# Pure_Digit.net
KiCad netlist of a schematic drawn in EAGLE
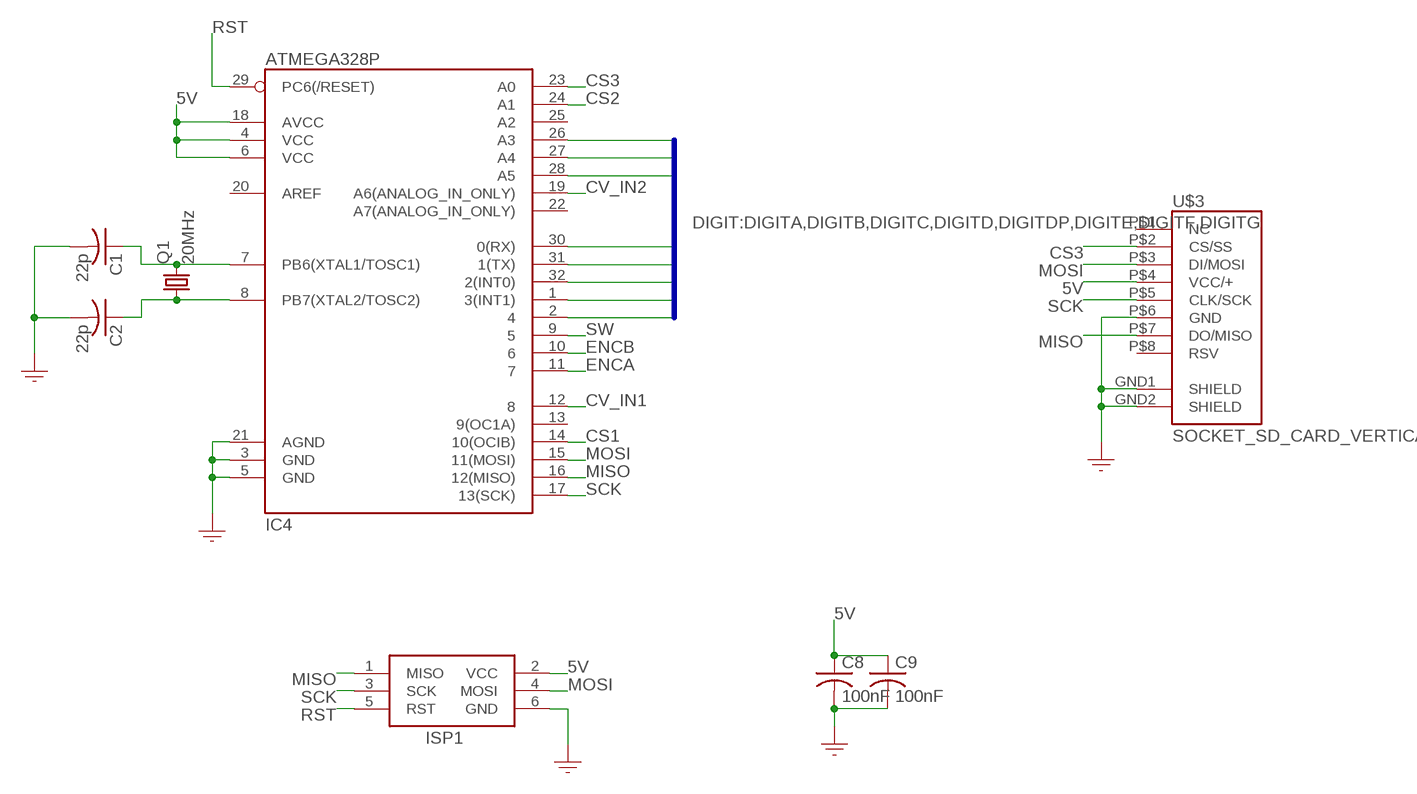
[diagram p0: schematic, sheet 1]
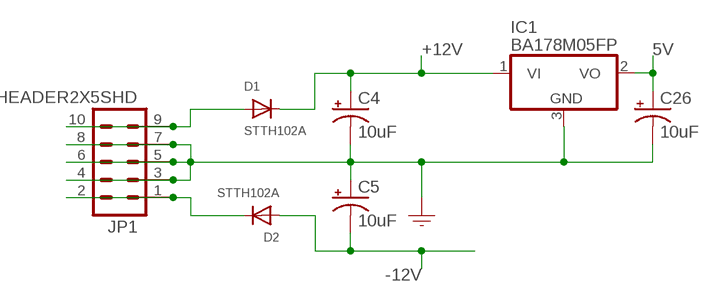
[diagram p1: schematic, sheet 2]
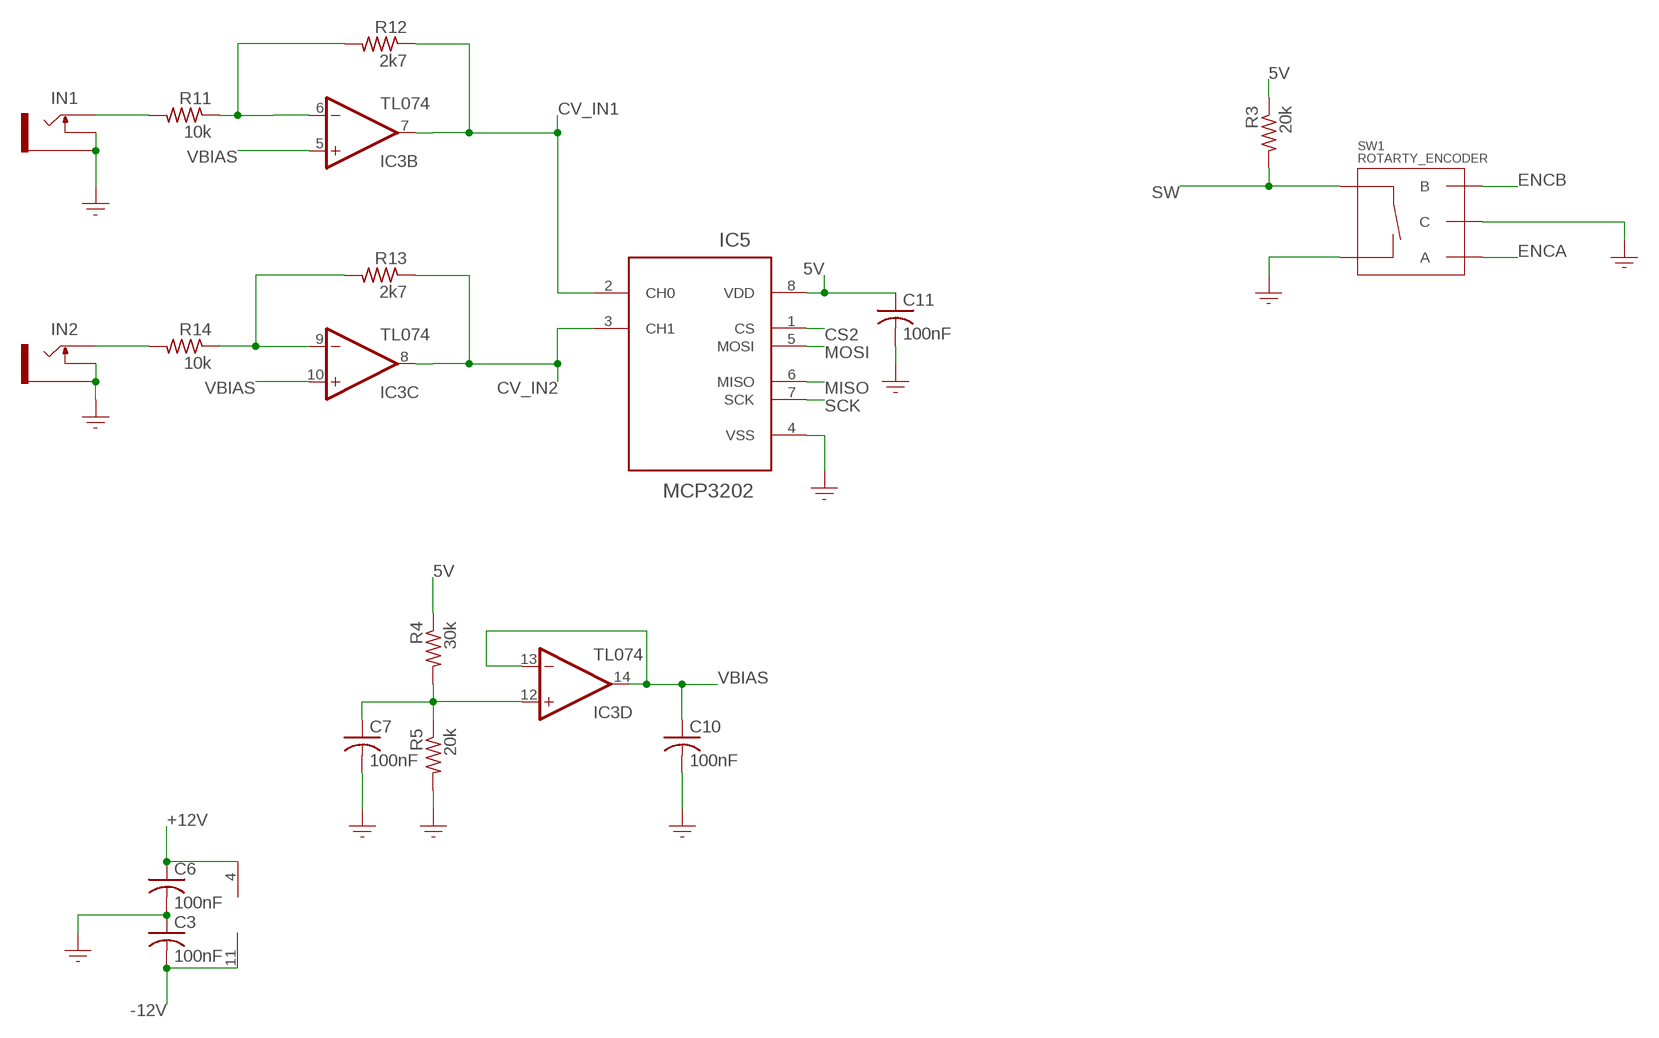
[diagram p2: schematic, sheet 3]
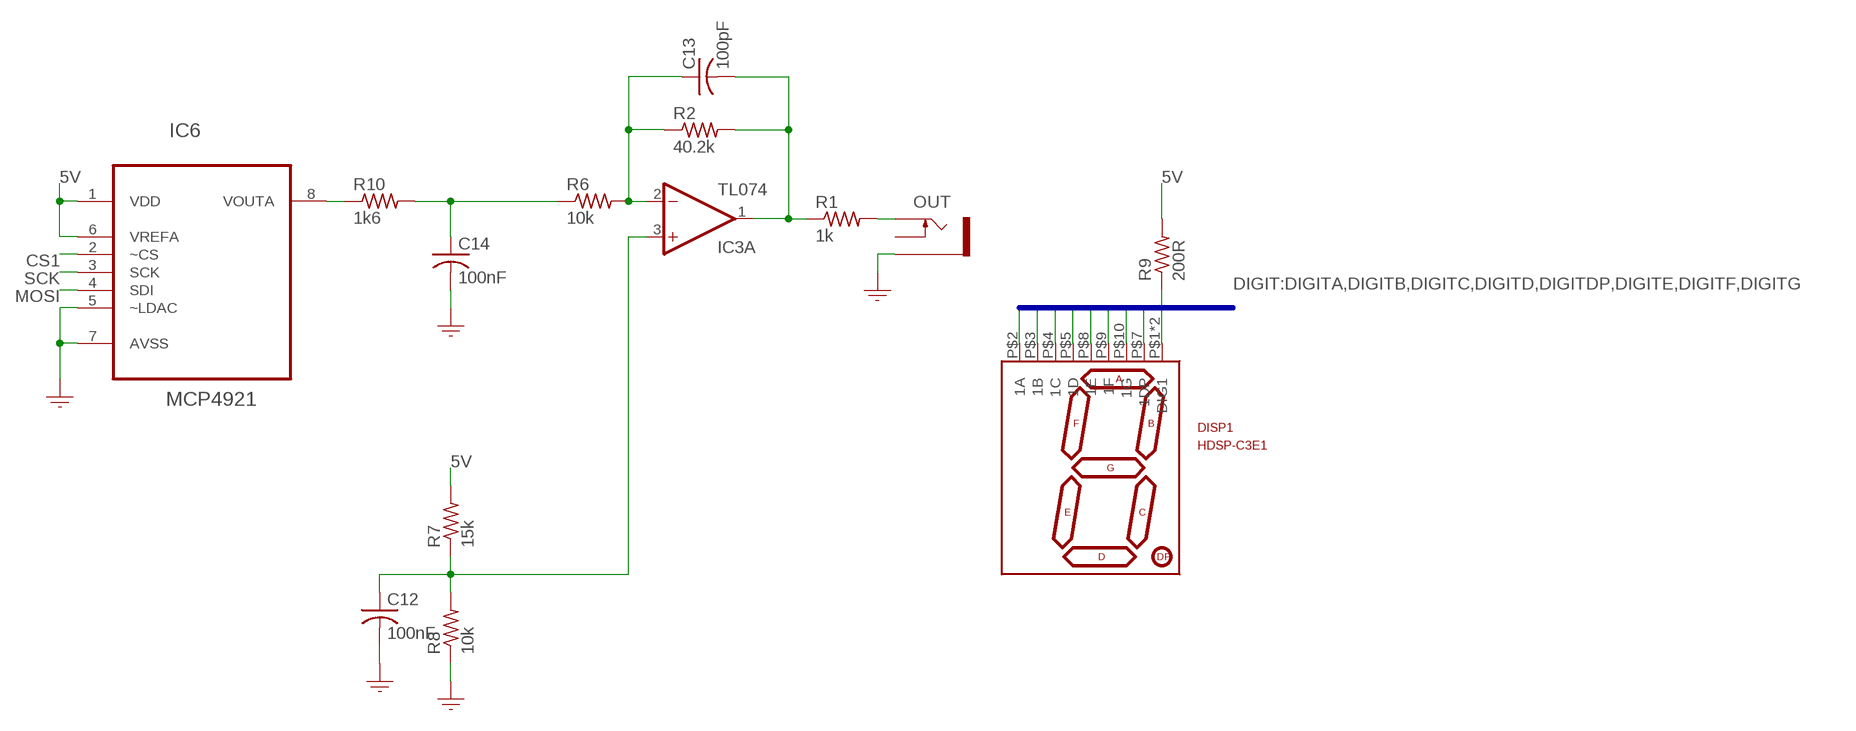
[diagram p3: schematic, sheet 4]

(export (version "E")
  (design (tool "Eeschema 10.0.6"))
  (components
    (comp (ref "C12")
      (value "100nF")
      (footprint "eagle-import:C0805")
      (libsource (lib "eagle-import") (part "CAPACITOR-USC0805"))
    )
    (comp (ref "C13")
      (value "100pF")
      (footprint "eagle-import:C0805")
      (libsource (lib "eagle-import") (part "CAPACITOR-USC0805"))
    )
    (comp (ref "C14")
      (value "100nF")
      (footprint "eagle-import:C0805")
      (libsource (lib "eagle-import") (part "CAPACITOR-USC0805"))
    )
    (comp (ref "DISP1")
      (value "HDSP-C3E1")
      (footprint "eagle-import:7-SEGMENT-1DIGIT")
      (libsource (lib "eagle-import") (part "DISPLAY_7-SEGMENT-1DIGIT"))
    )
    (comp (ref "IC3")
      (value "TL074")
      (footprint "eagle-import:SO14")
      (libsource (lib "eagle-import") (part "OPAMP_QUADD"))
    )
    (comp (ref "IC6")
      (value "MCP4921")
      (footprint "eagle-import:SOIC8")
      (libsource (lib "eagle-import") (part "DAC_SINGLE_12B_MCP4921"))
    )
    (comp (ref "OUT")
      (value "PJ301M-12")
      (footprint "eagle-import:PJ301M-12")
      (libsource (lib "eagle-import") (part "SOCKET_MONO_3.5MMPJ301M-12"))
    )
    (comp (ref "R1")
      (value "1k")
      (footprint "eagle-import:R0805")
      (libsource (lib "eagle-import") (part "RESISTOR_USR0805"))
    )
    (comp (ref "R2")
      (value "40.2k")
      (footprint "eagle-import:R0805")
      (libsource (lib "eagle-import") (part "RESISTOR_USR0805"))
    )
    (comp (ref "R6")
      (value "10k")
      (footprint "eagle-import:R0805")
      (libsource (lib "eagle-import") (part "RESISTOR_USR0805"))
    )
    (comp (ref "R7")
      (value "15k")
      (footprint "eagle-import:R0805")
      (libsource (lib "eagle-import") (part "RESISTOR_USR0805"))
    )
    (comp (ref "R8")
      (value "10k")
      (footprint "eagle-import:R0805")
      (libsource (lib "eagle-import") (part "RESISTOR_USR0805"))
    )
    (comp (ref "R9")
      (value "200R")
      (footprint "eagle-import:R0805")
      (libsource (lib "eagle-import") (part "RESISTOR_USR0805"))
    )
    (comp (ref "R10")
      (value "1k6")
      (footprint "eagle-import:R0805")
      (libsource (lib "eagle-import") (part "RESISTOR_USR0805"))
    )
    (comp (ref "C3")
      (value "100nF")
      (footprint "eagle-import:C0805")
      (libsource (lib "eagle-import") (part "CAPACITOR-USC0805"))
    )
    (comp (ref "C6")
      (value "100nF")
      (footprint "eagle-import:C0805")
      (libsource (lib "eagle-import") (part "CAPACITOR-USC0805"))
    )
    (comp (ref "C7")
      (value "100nF")
      (footprint "eagle-import:C0805")
      (libsource (lib "eagle-import") (part "CAPACITOR-USC0805"))
    )
    (comp (ref "C10")
      (value "100nF")
      (footprint "eagle-import:C0805")
      (libsource (lib "eagle-import") (part "CAPACITOR-USC0805"))
    )
    (comp (ref "C11")
      (value "100nF")
      (footprint "eagle-import:C0805")
      (libsource (lib "eagle-import") (part "CAPACITOR-USC0805"))
    )
    (comp (ref "IC5")
      (value "MCP3202")
      (footprint "eagle-import:SOIC--8")
      (libsource (lib "eagle-import") (part "ADC_DUAL_12B_MCP3202"))
    )
    (comp (ref "IN1")
      (value "PJ301M-12")
      (footprint "eagle-import:PJ301M-12")
      (libsource (lib "eagle-import") (part "SOCKET_MONO_3.5MMPJ301M-12"))
    )
    (comp (ref "IN2")
      (value "PJ301M-12")
      (footprint "eagle-import:PJ301M-12")
      (libsource (lib "eagle-import") (part "SOCKET_MONO_3.5MMPJ301M-12"))
    )
    (comp (ref "R3")
      (value "20k")
      (footprint "eagle-import:R0805")
      (libsource (lib "eagle-import") (part "RESISTOR_USR0805"))
    )
    (comp (ref "R4")
      (value "30k")
      (footprint "eagle-import:R0805")
      (libsource (lib "eagle-import") (part "RESISTOR_USR0805"))
    )
    (comp (ref "R5")
      (value "20k")
      (footprint "eagle-import:R0805")
      (libsource (lib "eagle-import") (part "RESISTOR_USR0805"))
    )
    (comp (ref "R11")
      (value "10k")
      (footprint "eagle-import:R0805")
      (libsource (lib "eagle-import") (part "RESISTOR_USR0805"))
    )
    (comp (ref "R12")
      (value "2k7")
      (footprint "eagle-import:R0805")
      (libsource (lib "eagle-import") (part "RESISTOR_USR0805"))
    )
    (comp (ref "R13")
      (value "2k7")
      (footprint "eagle-import:R0805")
      (libsource (lib "eagle-import") (part "RESISTOR_USR0805"))
    )
    (comp (ref "R14")
      (value "10k")
      (footprint "eagle-import:R0805")
      (libsource (lib "eagle-import") (part "RESISTOR_USR0805"))
    )
    (comp (ref "SW1")
      (value "ROTARTY_ENCODER")
      (footprint "eagle-import:ROTARY_ENC_PLAIN")
      (libsource (lib "eagle-import") (part "ROTARTY_ENCODER"))
    )
    (comp (ref "C4")
      (value "10uF")
      (footprint "eagle-import:153CLV-0505")
      (libsource (lib "eagle-import") (part "CAPACITOR_POL-US153CLV-0505"))
    )
    (comp (ref "C5")
      (value "10uF")
      (footprint "eagle-import:153CLV-0505")
      (libsource (lib "eagle-import") (part "CAPACITOR_POL-US153CLV-0505"))
    )
    (comp (ref "C26")
      (value "10uF")
      (footprint "eagle-import:153CLV-0505")
      (libsource (lib "eagle-import") (part "CAPACITOR_POL-US153CLV-0505"))
    )
    (comp (ref "D1")
      (value "STTH102A")
      (footprint "eagle-import:SMADIODE")
      (libsource (lib "eagle-import") (part "DIODESMA"))
    )
    (comp (ref "D2")
      (value "STTH102A")
      (footprint "eagle-import:SMADIODE")
      (libsource (lib "eagle-import") (part "DIODESMA"))
    )
    (comp (ref "IC1")
      (value "BA178M05FP")
      (footprint "eagle-import:TO252")
      (libsource (lib "eagle-import") (part "VOLTAGE_REG_POSDT05"))
    )
    (comp (ref "JP1")
      (value "HEADER2X5SHD")
      (footprint "eagle-import:2X5-SHROUDED")
      (libsource (lib "eagle-import") (part "HEADER2X5SHD"))
    )
    (comp (ref "C1")
      (value "22p")
      (footprint "eagle-import:C0805")
      (libsource (lib "eagle-import") (part "CAPACITOR-USC0805"))
    )
    (comp (ref "C2")
      (value "22p")
      (footprint "eagle-import:C0805")
      (libsource (lib "eagle-import") (part "CAPACITOR-USC0805"))
    )
    (comp (ref "C8")
      (value "100nF")
      (footprint "eagle-import:C0805")
      (libsource (lib "eagle-import") (part "CAPACITOR-USC0805"))
    )
    (comp (ref "C9")
      (value "100nF")
      (footprint "eagle-import:C0805")
      (libsource (lib "eagle-import") (part "CAPACITOR-USC0805"))
    )
    (comp (ref "IC4")
      (value "ATMEGA328P")
      (footprint "eagle-import:TQFP32-08")
      (libsource (lib "eagle-import") (part "MICROPROCESSOR_ATMEGA328_SMT"))
    )
    (comp (ref "ISP1")
      (value "HEADER2X3-6")
      (footprint "eagle-import:AVRISP")
      (libsource (lib "eagle-import") (part "HEADER2X3-6"))
    )
    (comp (ref "Q1")
      (value "20MHz")
      (footprint "eagle-import:SM49")
      (libsource (lib "eagle-import") (part "CRYSTALSM49"))
    )
    (comp (ref "U$3")
      (value "SOCKET_SD_CARD_VERTICAL")
      (footprint "eagle-import:PJS008U-3000")
      (libsource (lib "eagle-import") (part "SOCKET_SD_CARD_VERTICAL"))
    )
  )
  (nets
    (net (code "3") (name "+12V") (class "Default")
      (node (ref "C4") (pin "+") (pinfunction "+_+") (pintype "passive"))
      (node (ref "C6") (pin "1") (pinfunction "1_1") (pintype "passive"))
      (node (ref "D1") (pin "C") (pinfunction "C_C") (pintype "passive"))
      (node (ref "IC1") (pin "1") (pinfunction "VI_1") (pintype "input"))
      (node (ref "IC3") (pin "4") (pinfunction "V+_4") (pintype "power_in"))
    )
    (net (code "4") (name "-12V") (class "Default")
      (node (ref "C3") (pin "2") (pinfunction "2_2") (pintype "passive"))
      (node (ref "C5") (pin "-") (pinfunction "-_-") (pintype "passive"))
      (node (ref "D2") (pin "A") (pinfunction "A_A") (pintype "passive"))
      (node (ref "IC3") (pin "11") (pinfunction "V-_11") (pintype "power_in"))
    )
    (net (code "7") (name "5V") (class "Default")
      (node (ref "C11") (pin "1") (pinfunction "1_1") (pintype "passive"))
      (node (ref "C26") (pin "+") (pinfunction "+_+") (pintype "passive"))
      (node (ref "C8") (pin "1") (pinfunction "1_1") (pintype "passive"))
      (node (ref "C9") (pin "1") (pinfunction "1_1") (pintype "passive"))
      (node (ref "IC1") (pin "2") (pinfunction "VO_2") (pintype "passive"))
      (node (ref "IC4") (pin "18") (pinfunction "AVCC_18") (pintype "bidirectional"))
      (node (ref "IC4") (pin "4") (pinfunction "VCC_4") (pintype "bidirectional"))
      (node (ref "IC4") (pin "6") (pinfunction "VCC_6") (pintype "bidirectional"))
      (node (ref "IC5") (pin "8") (pinfunction "VDD_8") (pintype "bidirectional"))
      (node (ref "IC6") (pin "1") (pinfunction "VDD_1") (pintype "power_in"))
      (node (ref "IC6") (pin "6") (pinfunction "VREFA_6") (pintype "input"))
      (node (ref "ISP1") (pin "2") (pinfunction "VCC_2") (pintype "power_in"))
      (node (ref "R3") (pin "1") (pinfunction "1_1") (pintype "passive"))
      (node (ref "R4") (pin "1") (pinfunction "1_1") (pintype "passive"))
      (node (ref "R7") (pin "2") (pinfunction "2_2") (pintype "passive"))
      (node (ref "R9") (pin "2") (pinfunction "2_2") (pintype "passive"))
      (node (ref "U$3") (pin "P$4") (pinfunction "VCC/+_P$4") (pintype "bidirectional"))
    )
    (net (code "8") (name "CS1") (class "Default")
      (node (ref "IC4") (pin "14") (pinfunction "10(OCIB)_14") (pintype "bidirectional"))
      (node (ref "IC6") (pin "2") (pinfunction "~{CS}_2") (pintype "input"))
    )
    (net (code "9") (name "CS2") (class "Default")
      (node (ref "IC4") (pin "24") (pinfunction "A1_24") (pintype "bidirectional"))
      (node (ref "IC5") (pin "1") (pinfunction "CS_1") (pintype "bidirectional"))
    )
    (net (code "10") (name "CS3") (class "Default")
      (node (ref "IC4") (pin "23") (pinfunction "A0_23") (pintype "bidirectional"))
      (node (ref "U$3") (pin "P$2") (pinfunction "CS/SS_P$2") (pintype "bidirectional"))
    )
    (net (code "11") (name "CV_IN1") (class "Default")
      (node (ref "IC3") (pin "7") (pinfunction "OUT_7") (pintype "output"))
      (node (ref "IC4") (pin "12") (pinfunction "8_12") (pintype "bidirectional"))
      (node (ref "IC5") (pin "2") (pinfunction "CH0_2") (pintype "bidirectional"))
      (node (ref "R12") (pin "1") (pinfunction "1_1") (pintype "passive"))
    )
    (net (code "12") (name "CV_IN2") (class "Default")
      (node (ref "IC3") (pin "8") (pinfunction "OUT_8") (pintype "output"))
      (node (ref "IC4") (pin "19") (pinfunction "A6(ANALOG_IN_ONLY)_19") (pintype "bidirectional"))
      (node (ref "IC5") (pin "3") (pinfunction "CH1_3") (pintype "bidirectional"))
      (node (ref "R13") (pin "1") (pinfunction "1_1") (pintype "passive"))
    )
    (net (code "13") (name "DIGITA") (class "Default")
      (node (ref "DISP1") (pin "P$2") (pinfunction "1A_P$2") (pintype "bidirectional"))
      (node (ref "IC4") (pin "30") (pinfunction "0(RX)_30") (pintype "bidirectional"))
    )
    (net (code "14") (name "DIGITB") (class "Default")
      (node (ref "DISP1") (pin "P$3") (pinfunction "1B_P$3") (pintype "bidirectional"))
      (node (ref "IC4") (pin "28") (pinfunction "A5_28") (pintype "bidirectional"))
    )
    (net (code "15") (name "DIGITC") (class "Default")
      (node (ref "DISP1") (pin "P$4") (pinfunction "1C_P$4") (pintype "bidirectional"))
      (node (ref "IC4") (pin "27") (pinfunction "A4_27") (pintype "bidirectional"))
    )
    (net (code "16") (name "DIGITD") (class "Default")
      (node (ref "DISP1") (pin "P$5") (pinfunction "1D_P$5") (pintype "bidirectional"))
      (node (ref "IC4") (pin "26") (pinfunction "A3_26") (pintype "bidirectional"))
    )
    (net (code "17") (name "DIGITDP") (class "Default")
      (node (ref "DISP1") (pin "P$7") (pinfunction "1DP_P$7") (pintype "bidirectional"))
      (node (ref "IC4") (pin "1") (pinfunction "3(INT1)_1") (pintype "bidirectional"))
    )
    (net (code "18") (name "DIGITE") (class "Default")
      (node (ref "DISP1") (pin "P$8") (pinfunction "1E_P$8") (pintype "bidirectional"))
      (node (ref "IC4") (pin "2") (pinfunction "4_2") (pintype "bidirectional"))
    )
    (net (code "19") (name "DIGITF") (class "Default")
      (node (ref "DISP1") (pin "P$9") (pinfunction "1F_P$9") (pintype "bidirectional"))
      (node (ref "IC4") (pin "32") (pinfunction "2(INT0)_32") (pintype "bidirectional"))
    )
    (net (code "20") (name "DIGITG") (class "Default")
      (node (ref "DISP1") (pin "P$10") (pinfunction "1G_P$10") (pintype "bidirectional"))
      (node (ref "IC4") (pin "31") (pinfunction "1(TX)_31") (pintype "bidirectional"))
    )
    (net (code "21") (name "ENCA") (class "Default")
      (node (ref "IC4") (pin "11") (pinfunction "7_11") (pintype "bidirectional"))
      (node (ref "SW1") (pin "A") (pinfunction "A_A") (pintype "bidirectional"))
    )
    (net (code "22") (name "ENCB") (class "Default")
      (node (ref "IC4") (pin "10") (pinfunction "6_10") (pintype "bidirectional"))
      (node (ref "SW1") (pin "B") (pinfunction "B_B") (pintype "bidirectional"))
    )
    (net (code "23") (name "GND") (class "Default")
      (node (ref "C1") (pin "2") (pinfunction "2_2") (pintype "passive"))
      (node (ref "C10") (pin "2") (pinfunction "2_2") (pintype "passive"))
      (node (ref "C11") (pin "2") (pinfunction "2_2") (pintype "passive"))
      (node (ref "C12") (pin "2") (pinfunction "2_2") (pintype "passive"))
      (node (ref "C14") (pin "2") (pinfunction "2_2") (pintype "passive"))
      (node (ref "C2") (pin "2") (pinfunction "2_2") (pintype "passive"))
      (node (ref "C26") (pin "-") (pinfunction "-_-") (pintype "passive"))
      (node (ref "C3") (pin "1") (pinfunction "1_1") (pintype "passive"))
      (node (ref "C4") (pin "-") (pinfunction "-_-") (pintype "passive"))
      (node (ref "C5") (pin "+") (pinfunction "+_+") (pintype "passive"))
      (node (ref "C6") (pin "2") (pinfunction "2_2") (pintype "passive"))
      (node (ref "C7") (pin "2") (pinfunction "2_2") (pintype "passive"))
      (node (ref "C8") (pin "2") (pinfunction "2_2") (pintype "passive"))
      (node (ref "C9") (pin "2") (pinfunction "2_2") (pintype "passive"))
      (node (ref "IC1") (pin "3") (pinfunction "GND_3") (pintype "passive"))
      (node (ref "IC4") (pin "21") (pinfunction "AGND_21") (pintype "bidirectional"))
      (node (ref "IC4") (pin "3") (pinfunction "GND_3") (pintype "bidirectional"))
      (node (ref "IC4") (pin "5") (pinfunction "GND_5") (pintype "bidirectional"))
      (node (ref "IC5") (pin "4") (pinfunction "VSS_4") (pintype "bidirectional"))
      (node (ref "IC6") (pin "5") (pinfunction "~{LDAC}_5") (pintype "input"))
      (node (ref "IC6") (pin "7") (pinfunction "AVSS_7") (pintype "passive"))
      (node (ref "IN1") (pin "GND") (pinfunction "SLEEVE_GND") (pintype "passive"))
      (node (ref "IN1") (pin "NORM") (pinfunction "SWITCH_NORM") (pintype "passive"))
      (node (ref "IN2") (pin "GND") (pinfunction "SLEEVE_GND") (pintype "passive"))
      (node (ref "IN2") (pin "NORM") (pinfunction "SWITCH_NORM") (pintype "passive"))
      (node (ref "ISP1") (pin "6") (pinfunction "GND_6") (pintype "power_in"))
      (node (ref "JP1") (pin "3") (pinfunction "3_3") (pintype "passive"))
      (node (ref "JP1") (pin "4") (pinfunction "4_4") (pintype "passive"))
      (node (ref "JP1") (pin "5") (pinfunction "5_5") (pintype "passive"))
      (node (ref "JP1") (pin "6") (pinfunction "6_6") (pintype "passive"))
      (node (ref "JP1") (pin "7") (pinfunction "7_7") (pintype "passive"))
      (node (ref "JP1") (pin "8") (pinfunction "8_8") (pintype "passive"))
      (node (ref "OUT") (pin "GND") (pinfunction "SLEEVE_GND") (pintype "passive"))
      (node (ref "R5") (pin "2") (pinfunction "2_2") (pintype "passive"))
      (node (ref "R8") (pin "1") (pinfunction "1_1") (pintype "passive"))
      (node (ref "SW1") (pin "C") (pinfunction "C_C") (pintype "bidirectional"))
      (node (ref "SW1") (pin "SW-") (pinfunction "SW-_SW-") (pintype "bidirectional"))
      (node (ref "U$3") (pin "GND1") (pinfunction "SHIELD_GND1") (pintype "bidirectional"))
      (node (ref "U$3") (pin "GND2") (pinfunction "SHIELD_GND2") (pintype "bidirectional"))
      (node (ref "U$3") (pin "P$6") (pinfunction "GND_P$6") (pintype "bidirectional"))
    )
    (net (code "24") (name "MISO") (class "Default")
      (node (ref "IC4") (pin "16") (pinfunction "12(MISO)_16") (pintype "bidirectional"))
      (node (ref "IC5") (pin "6") (pinfunction "MISO_6") (pintype "bidirectional"))
      (node (ref "ISP1") (pin "1") (pinfunction "MISO_1") (pintype "input"))
      (node (ref "U$3") (pin "P$7") (pinfunction "DO/MISO_P$7") (pintype "bidirectional"))
    )
    (net (code "25") (name "MOSI") (class "Default")
      (node (ref "IC4") (pin "15") (pinfunction "11(MOSI)_15") (pintype "bidirectional"))
      (node (ref "IC5") (pin "5") (pinfunction "MOSI_5") (pintype "bidirectional"))
      (node (ref "IC6") (pin "4") (pinfunction "SDI_4") (pintype "input"))
      (node (ref "ISP1") (pin "4") (pinfunction "MOSI_4") (pintype "output"))
      (node (ref "U$3") (pin "P$3") (pinfunction "DI/MOSI_P$3") (pintype "bidirectional"))
    )
    (net (code "26") (name "Net-(C14-Pad1)") (class "Default")
      (node (ref "C14") (pin "1") (pinfunction "1_1") (pintype "passive"))
      (node (ref "R10") (pin "2") (pinfunction "2_2") (pintype "passive"))
      (node (ref "R6") (pin "1") (pinfunction "1_1") (pintype "passive"))
    )
    (net (code "27") (name "Net-(D1-PadA)") (class "Default")
      (node (ref "D1") (pin "A") (pinfunction "A_A") (pintype "passive"))
      (node (ref "JP1") (pin "10") (pinfunction "10_10") (pintype "passive"))
      (node (ref "JP1") (pin "9") (pinfunction "9_9") (pintype "passive"))
    )
    (net (code "28") (name "Net-(D2-PadC)") (class "Default")
      (node (ref "D2") (pin "C") (pinfunction "C_C") (pintype "passive"))
      (node (ref "JP1") (pin "1") (pinfunction "1_1") (pintype "passive"))
      (node (ref "JP1") (pin "2") (pinfunction "2_2") (pintype "passive"))
    )
    (net (code "29") (name "Net-(DISP1-DIG1-PadP$1)") (class "Default")
      (node (ref "DISP1") (pin "P$1") (pinfunction "DIG1_P$1") (pintype "bidirectional"))
      (node (ref "DISP1") (pin "P$6") (pinfunction "DIG1_P$6") (pintype "bidirectional"))
      (node (ref "R9") (pin "1") (pinfunction "1_1") (pintype "passive"))
    )
    (net (code "30") (name "Net-(IC3A-+IN)") (class "Default")
      (node (ref "C12") (pin "1") (pinfunction "1_1") (pintype "passive"))
      (node (ref "IC3") (pin "3") (pinfunction "+IN_3") (pintype "input"))
      (node (ref "R7") (pin "1") (pinfunction "1_1") (pintype "passive"))
      (node (ref "R8") (pin "2") (pinfunction "2_2") (pintype "passive"))
    )
    (net (code "31") (name "Net-(IC3A--IN)") (class "Default")
      (node (ref "C13") (pin "1") (pinfunction "1_1") (pintype "passive"))
      (node (ref "IC3") (pin "2") (pinfunction "-IN_2") (pintype "input"))
      (node (ref "R2") (pin "1") (pinfunction "1_1") (pintype "passive"))
      (node (ref "R6") (pin "2") (pinfunction "2_2") (pintype "passive"))
    )
    (net (code "32") (name "Net-(IC3A-OUT)") (class "Default")
      (node (ref "C13") (pin "2") (pinfunction "2_2") (pintype "passive"))
      (node (ref "IC3") (pin "1") (pinfunction "OUT_1") (pintype "output"))
      (node (ref "R1") (pin "1") (pinfunction "1_1") (pintype "passive"))
      (node (ref "R2") (pin "2") (pinfunction "2_2") (pintype "passive"))
    )
    (net (code "33") (name "Net-(IC3B--IN)") (class "Default")
      (node (ref "IC3") (pin "6") (pinfunction "-IN_6") (pintype "input"))
      (node (ref "R11") (pin "1") (pinfunction "1_1") (pintype "passive"))
      (node (ref "R12") (pin "2") (pinfunction "2_2") (pintype "passive"))
    )
    (net (code "34") (name "Net-(IC3C--IN)") (class "Default")
      (node (ref "IC3") (pin "9") (pinfunction "-IN_9") (pintype "input"))
      (node (ref "R13") (pin "2") (pinfunction "2_2") (pintype "passive"))
      (node (ref "R14") (pin "1") (pinfunction "1_1") (pintype "passive"))
    )
    (net (code "35") (name "Net-(IC3D-+IN)") (class "Default")
      (node (ref "C7") (pin "1") (pinfunction "1_1") (pintype "passive"))
      (node (ref "IC3") (pin "12") (pinfunction "+IN_12") (pintype "input"))
      (node (ref "R4") (pin "2") (pinfunction "2_2") (pintype "passive"))
      (node (ref "R5") (pin "1") (pinfunction "1_1") (pintype "passive"))
    )
    (net (code "36") (name "Net-(IC4-PB6(XTAL1{slash}TOSC1))") (class "Default")
      (node (ref "C1") (pin "1") (pinfunction "1_1") (pintype "passive"))
      (node (ref "IC4") (pin "7") (pinfunction "PB6(XTAL1/TOSC1)_7") (pintype "bidirectional"))
      (node (ref "Q1") (pin "2") (pinfunction "2_2") (pintype "passive"))
    )
    (net (code "37") (name "Net-(IC4-PB7(XTAL2{slash}TOSC2))") (class "Default")
      (node (ref "C2") (pin "1") (pinfunction "1_1") (pintype "passive"))
      (node (ref "IC4") (pin "8") (pinfunction "PB7(XTAL2/TOSC2)_8") (pintype "bidirectional"))
      (node (ref "Q1") (pin "1") (pinfunction "1_1") (pintype "passive"))
    )
    (net (code "38") (name "Net-(IC6-VOUTA)") (class "Default")
      (node (ref "IC6") (pin "8") (pinfunction "VOUTA_8") (pintype "output"))
      (node (ref "R10") (pin "1") (pinfunction "1_1") (pintype "passive"))
    )
    (net (code "39") (name "Net-(IN1-PadTIP)") (class "Default")
      (node (ref "IN1") (pin "TIP") (pinfunction "TIP_TIP") (pintype "passive"))
      (node (ref "R11") (pin "2") (pinfunction "2_2") (pintype "passive"))
    )
    (net (code "40") (name "Net-(IN2-PadTIP)") (class "Default")
      (node (ref "IN2") (pin "TIP") (pinfunction "TIP_TIP") (pintype "passive"))
      (node (ref "R14") (pin "2") (pinfunction "2_2") (pintype "passive"))
    )
    (net (code "41") (name "Net-(OUT-PadTIP)") (class "Default")
      (node (ref "OUT") (pin "TIP") (pinfunction "TIP_TIP") (pintype "passive"))
      (node (ref "R1") (pin "2") (pinfunction "2_2") (pintype "passive"))
    )
    (net (code "42") (name "RST") (class "Default")
      (node (ref "IC4") (pin "29") (pinfunction "PC6(/RESET)_29") (pintype "bidirectional"))
      (node (ref "ISP1") (pin "5") (pinfunction "RST_5") (pintype "output"))
    )
    (net (code "43") (name "SCK") (class "Default")
      (node (ref "IC4") (pin "17") (pinfunction "13(SCK)_17") (pintype "bidirectional"))
      (node (ref "IC5") (pin "7") (pinfunction "SCK_7") (pintype "bidirectional"))
      (node (ref "IC6") (pin "3") (pinfunction "SCK_3") (pintype "input"))
      (node (ref "ISP1") (pin "3") (pinfunction "SCK_3") (pintype "output"))
      (node (ref "U$3") (pin "P$5") (pinfunction "CLK/SCK_P$5") (pintype "bidirectional"))
    )
    (net (code "44") (name "SW") (class "Default")
      (node (ref "IC4") (pin "9") (pinfunction "5_9") (pintype "bidirectional"))
      (node (ref "R3") (pin "2") (pinfunction "2_2") (pintype "passive"))
      (node (ref "SW1") (pin "SW+") (pinfunction "SW+_SW+") (pintype "bidirectional"))
    )
    (net (code "45") (name "VBIAS") (class "Default")
      (node (ref "C10") (pin "1") (pinfunction "1_1") (pintype "passive"))
      (node (ref "IC3") (pin "10") (pinfunction "+IN_10") (pintype "input"))
      (node (ref "IC3") (pin "13") (pinfunction "-IN_13") (pintype "input"))
      (node (ref "IC3") (pin "14") (pinfunction "OUT_14") (pintype "output"))
      (node (ref "IC3") (pin "5") (pinfunction "+IN_5") (pintype "input"))
    )
    (net (code "46") (name "unconnected-(IC4-9(OC1A)-Pad13)") (class "Default")
      (node (ref "IC4") (pin "13") (pinfunction "9(OC1A)_13") (pintype "bidirectional"))
    )
    (net (code "47") (name "unconnected-(IC4-A2-Pad25)") (class "Default")
      (node (ref "IC4") (pin "25") (pinfunction "A2_25") (pintype "bidirectional"))
    )
    (net (code "48") (name "unconnected-(IC4-A7(ANALOG_IN_ONLY)-Pad22)") (class "Default")
      (node (ref "IC4") (pin "22") (pinfunction "A7(ANALOG_IN_ONLY)_22") (pintype "bidirectional"))
    )
    (net (code "49") (name "unconnected-(IC4-AREF-Pad20)") (class "Default")
      (node (ref "IC4") (pin "20") (pinfunction "AREF_20") (pintype "bidirectional"))
    )
    (net (code "50") (name "unconnected-(OUT-SWITCH-PadNORM)") (class "Default")
      (node (ref "OUT") (pin "NORM") (pinfunction "SWITCH_NORM") (pintype "passive"))
    )
    (net (code "51") (name "unconnected-(U$3-NC-PadP$1)") (class "Default")
      (node (ref "U$3") (pin "P$1") (pinfunction "NC_P$1") (pintype "bidirectional"))
    )
    (net (code "52") (name "unconnected-(U$3-RSV-PadP$8)") (class "Default")
      (node (ref "U$3") (pin "P$8") (pinfunction "RSV_P$8") (pintype "bidirectional"))
    )
  )
)
